# ACESDS1307BoBV2.net
KiCad netlist of a schematic drawn in EAGLE
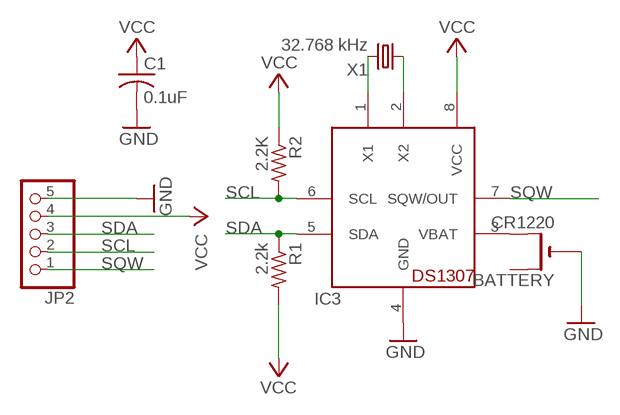
[diagram p0: schematic, sheet 1]

(export (version "E")
  (design (tool "Eeschema 10.0.6"))
  (components
    (comp (ref "BATTERY")
      (value "CR1220")
      (footprint "eagle-import:CR1220-THM")
      (libsource (lib "eagle-import") (part "CR1220THM"))
    )
    (comp (ref "C1")
      (value "0.1uF")
      (footprint "eagle-import:C025-025X050")
      (libsource (lib "eagle-import") (part "C-US025-025X050"))
    )
    (comp (ref "IC3")
      (value "DS1307")
      (footprint "eagle-import:DIL08")
      (libsource (lib "eagle-import") (part "DS1307"))
    )
    (comp (ref "JP2")
      (value "PINHD-1X5")
      (footprint "eagle-import:1X05")
      (libsource (lib "eagle-import") (part "PINHD-1X5"))
    )
    (comp (ref "R1")
      (value "2.2k")
      (footprint "eagle-import:0207_10")
      (libsource (lib "eagle-import") (part "R-US_0207/10"))
    )
    (comp (ref "R2")
      (value "2.2K")
      (footprint "eagle-import:0207_10")
      (libsource (lib "eagle-import") (part "R-US_0207/10"))
    )
    (comp (ref "X1")
      (value "32.768 kHz")
      (footprint "eagle-import:TC38H")
      (libsource (lib "eagle-import") (part "CRYTALTC38H"))
    )
  )
  (nets
    (net (code "1") (name "/SCL") (class "Default")
      (node (ref "IC3") (pin "6") (pinfunction "SCL_6") (pintype "bidirectional"))
      (node (ref "JP2") (pin "2") (pinfunction "2_2") (pintype "passive"))
      (node (ref "R2") (pin "2") (pinfunction "2_2") (pintype "passive"))
    )
    (net (code "2") (name "/SDA") (class "Default")
      (node (ref "IC3") (pin "5") (pinfunction "SDA_5") (pintype "bidirectional"))
      (node (ref "JP2") (pin "3") (pinfunction "3_3") (pintype "passive"))
      (node (ref "R1") (pin "1") (pinfunction "1_1") (pintype "passive"))
    )
    (net (code "3") (name "/SQW") (class "Default")
      (node (ref "IC3") (pin "7") (pinfunction "SQW/OUT_7") (pintype "bidirectional"))
      (node (ref "JP2") (pin "1") (pinfunction "1_1") (pintype "passive"))
    )
    (net (code "4") (name "GND") (class "Default")
      (node (ref "BATTERY") (pin "-") (pinfunction "-_-") (pintype "passive"))
      (node (ref "C1") (pin "2") (pinfunction "2_2") (pintype "passive"))
      (node (ref "IC3") (pin "4") (pinfunction "GND_4") (pintype "power_in"))
      (node (ref "JP2") (pin "5") (pinfunction "5_5") (pintype "passive"))
    )
    (net (code "5") (name "Net-(BATTERY-+1)") (class "Default")
      (node (ref "BATTERY") (pin "+2") (pinfunction "+1_+2") (pintype "passive"))
      (node (ref "IC3") (pin "3") (pinfunction "VBAT_3") (pintype "power_in"))
    )
    (net (code "6") (name "Net-(IC3-X1)") (class "Default")
      (node (ref "IC3") (pin "1") (pinfunction "X1_1") (pintype "passive"))
      (node (ref "X1") (pin "2") (pinfunction "2_2") (pintype "passive"))
    )
    (net (code "7") (name "Net-(IC3-X2)") (class "Default")
      (node (ref "IC3") (pin "2") (pinfunction "X2_2") (pintype "passive"))
      (node (ref "X1") (pin "1") (pinfunction "1_1") (pintype "passive"))
    )
    (net (code "8") (name "VCC") (class "Default")
      (node (ref "C1") (pin "1") (pinfunction "1_1") (pintype "passive"))
      (node (ref "IC3") (pin "8") (pinfunction "VCC_8") (pintype "power_in"))
      (node (ref "JP2") (pin "4") (pinfunction "4_4") (pintype "passive"))
      (node (ref "R1") (pin "2") (pinfunction "2_2") (pintype "passive"))
      (node (ref "R2") (pin "1") (pinfunction "1_1") (pintype "passive"))
    )
    (net (code "9") (name "unconnected-(BATTERY-+-Pad+1)") (class "Default")
      (node (ref "BATTERY") (pin "+1") (pinfunction "+_+1") (pintype "passive"))
    )
  )
)
